# XMOS.net
KiCad netlist of a schematic drawn in Altium Designer
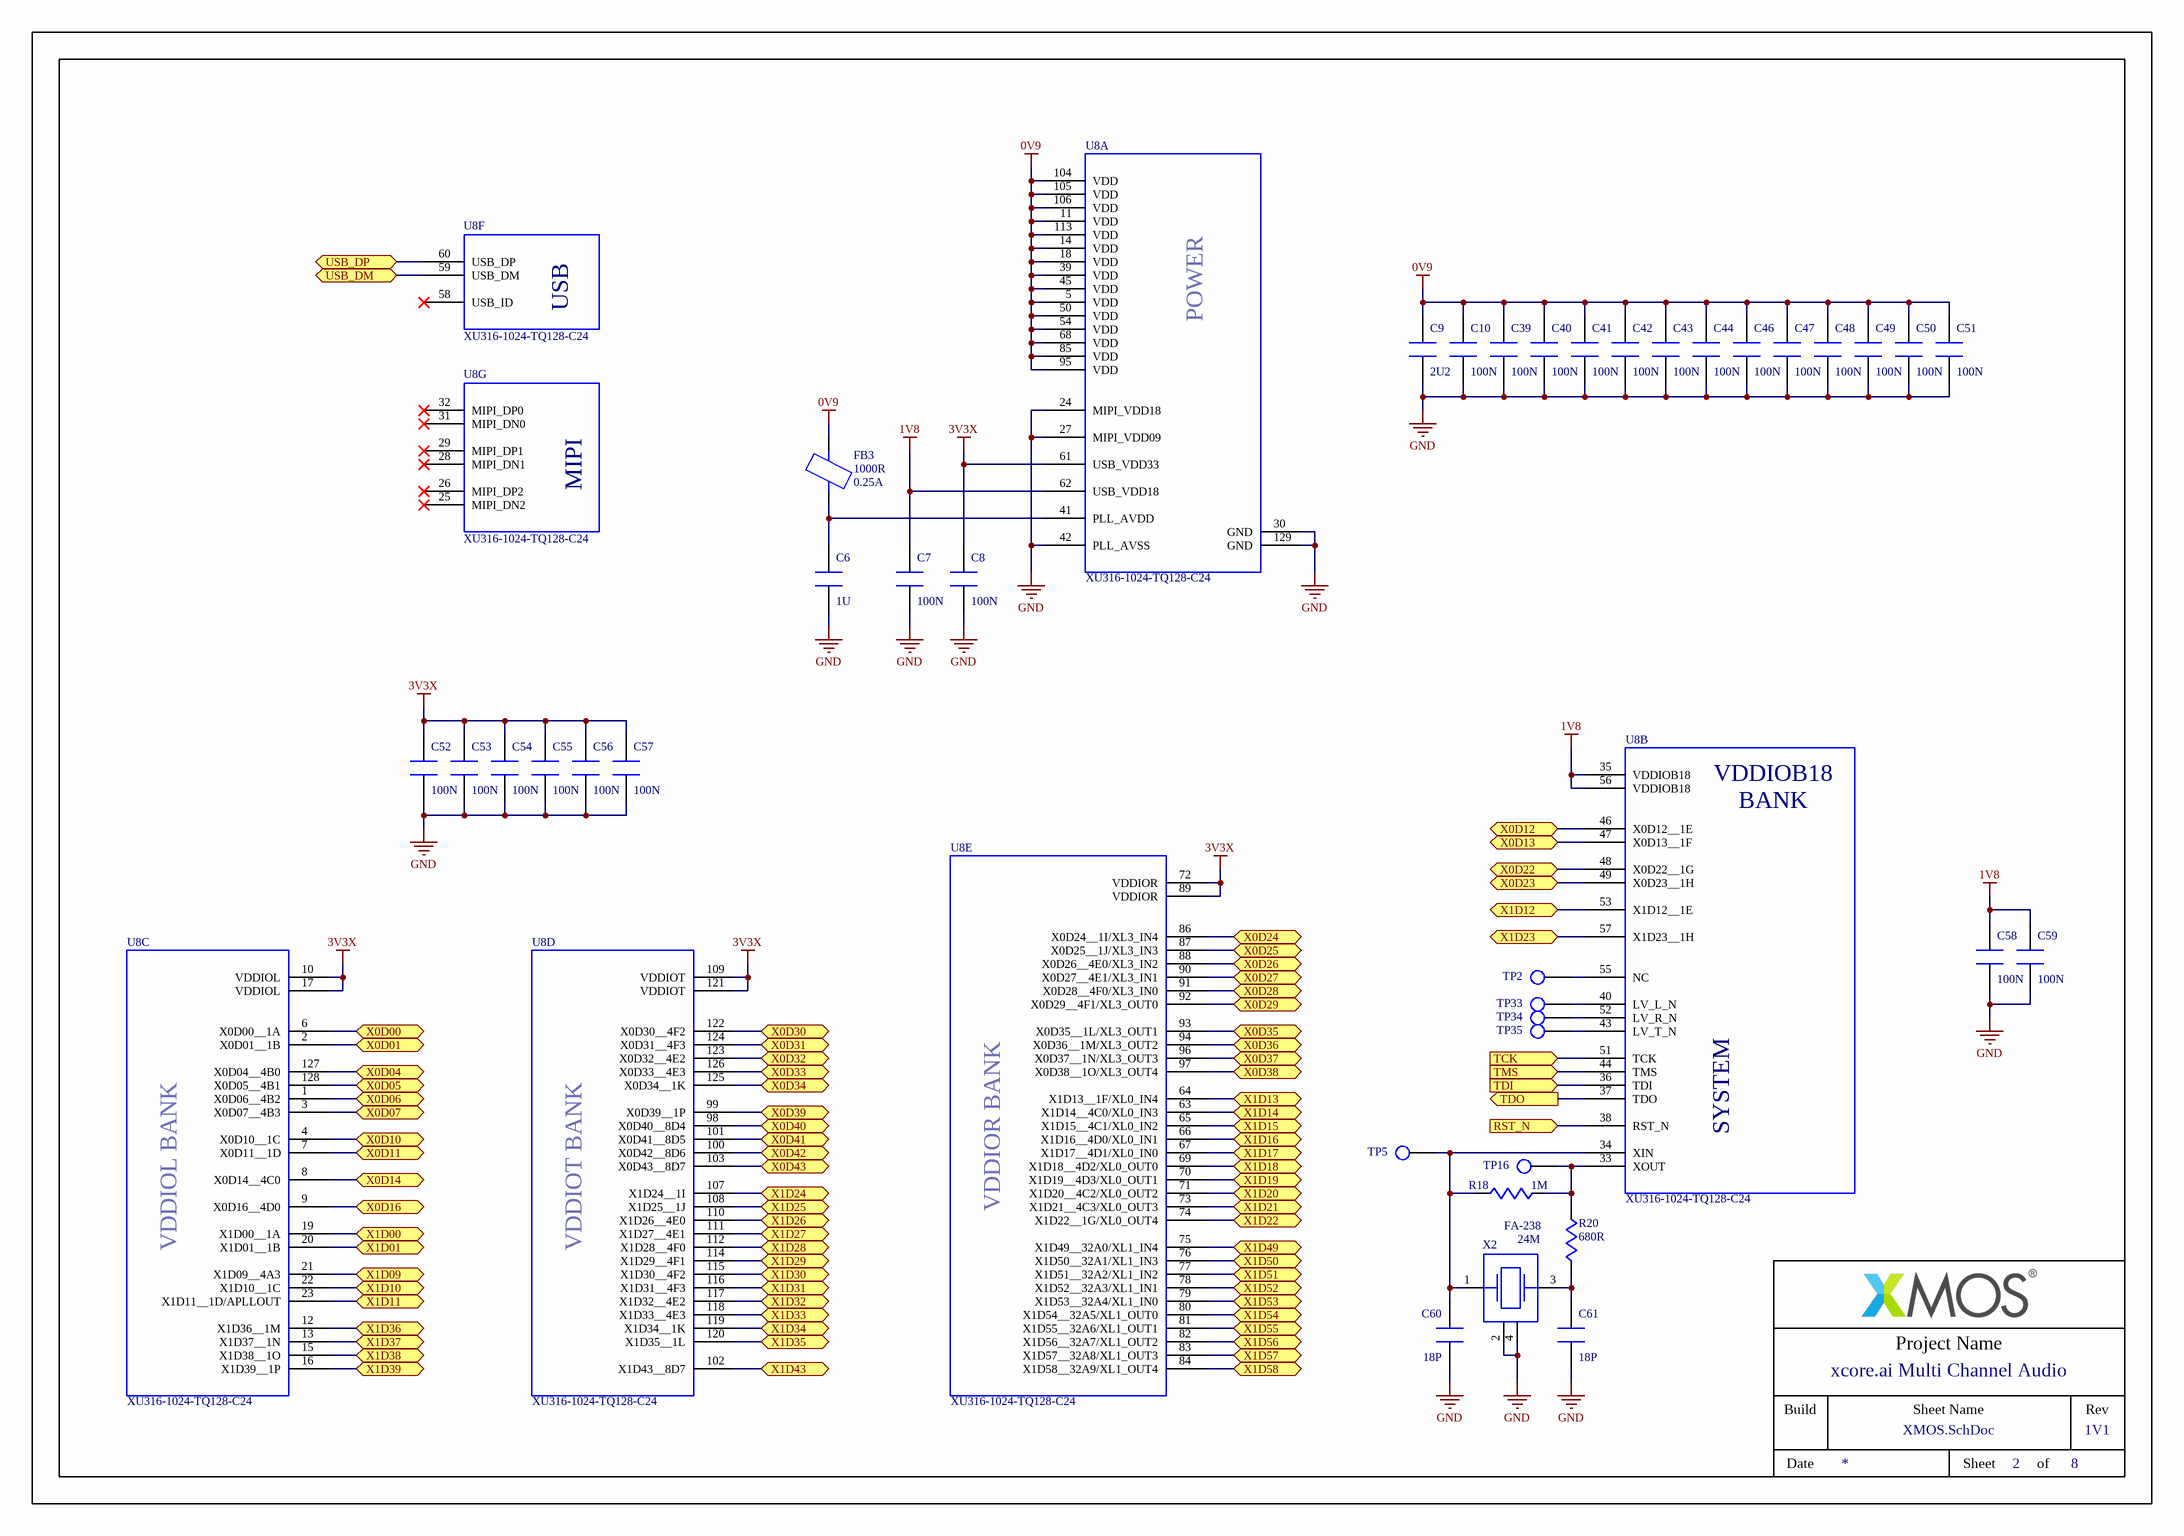
[diagram p0: XMOS.SchDoc]

(export (version "E")
  (design (tool "Eeschema 10.0.6"))
  (components
    (comp (ref "C6")
      (value "1U")
      (footprint "CAPC1005X55N")
      (description "CHIP CAPACITOR, CERAMIC, 1.0UF, 16V, 10%, X5R, 0402")
      (fields (field (name "PART NUMBER") "STD-06-0140") (field (name "TOLERANCE") "20%"))
      (libsource (lib "JG_StandardLibrary") (part "CAP_NP"))
    )
    (comp (ref "C7")
      (value "100N")
      (footprint "CAPC1005X55N")
      (description "CHIP CAPACITOR, CERAMIC, 100NF, 16V, 10%, X7R, 0402")
      (fields (field (name "PART NUMBER") "STD-06-0048") (field (name "TOLERANCE") "10%"))
      (libsource (lib "JG_StandardLibrary") (part "CAP_NP"))
    )
    (comp (ref "C8")
      (value "100N")
      (footprint "CAPC1005X55N")
      (description "CHIP CAPACITOR, CERAMIC, 100NF, 16V, 10%, X7R, 0402")
      (fields (field (name "PART NUMBER") "STD-06-0048") (field (name "TOLERANCE") "10%"))
      (libsource (lib "JG_StandardLibrary") (part "CAP_NP"))
    )
    (comp (ref "C9")
      (value "2U2")
      (footprint "CAPC1005X55N")
      (description "CHIP CAPACITOR, CERAMIC, 2.2UF, 6.3V, 10%, X5R, 0402")
      (fields (field (name "PART NUMBER") "GEN-03-0029") (field (name "TOLERANCE") "10%"))
      (libsource (lib "JG_GeneralLibrary") (part "CAP_NP"))
    )
    (comp (ref "C10")
      (value "100N")
      (footprint "CAPC1005X55N")
      (description "CHIP CAPACITOR, CERAMIC, 100NF, 16V, 10%, X7R, 0402")
      (fields (field (name "PART NUMBER") "STD-06-0048") (field (name "TOLERANCE") "10%"))
      (libsource (lib "JG_StandardLibrary") (part "CAP_NP"))
    )
    (comp (ref "C39")
      (value "100N")
      (footprint "CAPC1005X55N")
      (description "CHIP CAPACITOR, CERAMIC, 100NF, 16V, 10%, X7R, 0402")
      (fields (field (name "PART NUMBER") "STD-06-0048") (field (name "TOLERANCE") "10%"))
      (libsource (lib "JG_StandardLibrary") (part "CAP_NP"))
    )
    (comp (ref "C40")
      (value "100N")
      (footprint "CAPC1005X55N")
      (description "CHIP CAPACITOR, CERAMIC, 100NF, 16V, 10%, X7R, 0402")
      (fields (field (name "PART NUMBER") "STD-06-0048") (field (name "TOLERANCE") "10%"))
      (libsource (lib "JG_StandardLibrary") (part "CAP_NP"))
    )
    (comp (ref "C41")
      (value "100N")
      (footprint "CAPC1005X55N")
      (description "CHIP CAPACITOR, CERAMIC, 100NF, 16V, 10%, X7R, 0402")
      (fields (field (name "PART NUMBER") "STD-06-0048") (field (name "TOLERANCE") "10%"))
      (libsource (lib "JG_StandardLibrary") (part "CAP_NP"))
    )
    (comp (ref "C42")
      (value "100N")
      (footprint "CAPC1005X55N")
      (description "CHIP CAPACITOR, CERAMIC, 100NF, 16V, 10%, X7R, 0402")
      (fields (field (name "PART NUMBER") "STD-06-0048") (field (name "TOLERANCE") "10%"))
      (libsource (lib "JG_StandardLibrary") (part "CAP_NP"))
    )
    (comp (ref "C43")
      (value "100N")
      (footprint "CAPC1005X55N")
      (description "CHIP CAPACITOR, CERAMIC, 100NF, 16V, 10%, X7R, 0402")
      (fields (field (name "PART NUMBER") "STD-06-0048") (field (name "TOLERANCE") "10%"))
      (libsource (lib "JG_StandardLibrary") (part "CAP_NP"))
    )
    (comp (ref "C44")
      (value "100N")
      (footprint "CAPC1005X55N")
      (description "CHIP CAPACITOR, CERAMIC, 100NF, 16V, 10%, X7R, 0402")
      (fields (field (name "PART NUMBER") "STD-06-0048") (field (name "TOLERANCE") "10%"))
      (libsource (lib "JG_StandardLibrary") (part "CAP_NP"))
    )
    (comp (ref "C46")
      (value "100N")
      (footprint "CAPC1005X55N")
      (description "CHIP CAPACITOR, CERAMIC, 100NF, 16V, 10%, X7R, 0402")
      (fields (field (name "PART NUMBER") "STD-06-0048") (field (name "TOLERANCE") "10%"))
      (libsource (lib "JG_StandardLibrary") (part "CAP_NP"))
    )
    (comp (ref "C47")
      (value "100N")
      (footprint "CAPC1005X55N")
      (description "CHIP CAPACITOR, CERAMIC, 100NF, 16V, 10%, X7R, 0402")
      (fields (field (name "PART NUMBER") "STD-06-0048") (field (name "TOLERANCE") "10%"))
      (libsource (lib "JG_StandardLibrary") (part "CAP_NP"))
    )
    (comp (ref "C48")
      (value "100N")
      (footprint "CAPC1005X55N")
      (description "CHIP CAPACITOR, CERAMIC, 100NF, 16V, 10%, X7R, 0402")
      (fields (field (name "PART NUMBER") "STD-06-0048") (field (name "TOLERANCE") "10%"))
      (libsource (lib "JG_StandardLibrary") (part "CAP_NP"))
    )
    (comp (ref "C49")
      (value "100N")
      (footprint "CAPC1005X55N")
      (description "CHIP CAPACITOR, CERAMIC, 100NF, 16V, 10%, X7R, 0402")
      (fields (field (name "PART NUMBER") "STD-06-0048") (field (name "TOLERANCE") "10%"))
      (libsource (lib "JG_StandardLibrary") (part "CAP_NP"))
    )
    (comp (ref "C50")
      (value "100N")
      (footprint "CAPC1005X55N")
      (description "CHIP CAPACITOR, CERAMIC, 100NF, 16V, 10%, X7R, 0402")
      (fields (field (name "PART NUMBER") "STD-06-0048") (field (name "TOLERANCE") "10%"))
      (libsource (lib "JG_StandardLibrary") (part "CAP_NP"))
    )
    (comp (ref "C51")
      (value "100N")
      (footprint "CAPC1005X55N")
      (description "CHIP CAPACITOR, CERAMIC, 100NF, 16V, 10%, X7R, 0402")
      (fields (field (name "PART NUMBER") "STD-06-0048") (field (name "TOLERANCE") "10%"))
      (libsource (lib "JG_StandardLibrary") (part "CAP_NP"))
    )
    (comp (ref "C52")
      (value "100N")
      (footprint "CAPC1005X55N")
      (description "CHIP CAPACITOR, CERAMIC, 100NF, 16V, 10%, X7R, 0402")
      (fields (field (name "PART NUMBER") "STD-06-0048") (field (name "TOLERANCE") "10%"))
      (libsource (lib "JG_StandardLibrary") (part "CAP_NP"))
    )
    (comp (ref "C53")
      (value "100N")
      (footprint "CAPC1005X55N")
      (description "CHIP CAPACITOR, CERAMIC, 100NF, 16V, 10%, X7R, 0402")
      (fields (field (name "PART NUMBER") "STD-06-0048") (field (name "TOLERANCE") "10%"))
      (libsource (lib "JG_StandardLibrary") (part "CAP_NP"))
    )
    (comp (ref "C54")
      (value "100N")
      (footprint "CAPC1005X55N")
      (description "CHIP CAPACITOR, CERAMIC, 100NF, 16V, 10%, X7R, 0402")
      (fields (field (name "PART NUMBER") "STD-06-0048") (field (name "TOLERANCE") "10%"))
      (libsource (lib "JG_StandardLibrary") (part "CAP_NP"))
    )
    (comp (ref "C55")
      (value "100N")
      (footprint "CAPC1005X55N")
      (description "CHIP CAPACITOR, CERAMIC, 100NF, 16V, 10%, X7R, 0402")
      (fields (field (name "PART NUMBER") "STD-06-0048") (field (name "TOLERANCE") "10%"))
      (libsource (lib "JG_StandardLibrary") (part "CAP_NP"))
    )
    (comp (ref "C56")
      (value "100N")
      (footprint "CAPC1005X55N")
      (description "CHIP CAPACITOR, CERAMIC, 100NF, 16V, 10%, X7R, 0402")
      (fields (field (name "PART NUMBER") "STD-06-0048") (field (name "TOLERANCE") "10%"))
      (libsource (lib "JG_StandardLibrary") (part "CAP_NP"))
    )
    (comp (ref "C57")
      (value "100N")
      (footprint "CAPC1005X55N")
      (description "CHIP CAPACITOR, CERAMIC, 100NF, 16V, 10%, X7R, 0402")
      (fields (field (name "PART NUMBER") "STD-06-0048") (field (name "TOLERANCE") "10%"))
      (libsource (lib "JG_StandardLibrary") (part "CAP_NP"))
    )
    (comp (ref "C58")
      (value "100N")
      (footprint "CAPC1005X55N")
      (description "CHIP CAPACITOR, CERAMIC, 100NF, 16V, 10%, X7R, 0402")
      (fields (field (name "PART NUMBER") "STD-06-0048") (field (name "TOLERANCE") "10%"))
      (libsource (lib "JG_StandardLibrary") (part "CAP_NP"))
    )
    (comp (ref "C59")
      (value "100N")
      (footprint "CAPC1005X55N")
      (description "CHIP CAPACITOR, CERAMIC, 100NF, 16V, 10%, X7R, 0402")
      (fields (field (name "PART NUMBER") "STD-06-0048") (field (name "TOLERANCE") "10%"))
      (libsource (lib "JG_StandardLibrary") (part "CAP_NP"))
    )
    (comp (ref "C60")
      (value "18P")
      (footprint "CAPC1005X55N")
      (description "CHIP CAPACITOR, CERAMIC, 18PF, 50V, 5%, NP0, 0402")
      (fields (field (name "PART NUMBER") "STD-06-0016") (field (name "TOLERANCE") "5%"))
      (libsource (lib "JG_StandardLibrary") (part "CAP_NP"))
    )
    (comp (ref "C61")
      (value "18P")
      (footprint "CAPC1005X55N")
      (description "CHIP CAPACITOR, CERAMIC, 18PF, 50V, 5%, NP0, 0402")
      (fields (field (name "PART NUMBER") "STD-06-0016") (field (name "TOLERANCE") "5%"))
      (libsource (lib "JG_StandardLibrary") (part "CAP_NP"))
    )
    (comp (ref "FB3")
      (value "1000R")
      (footprint "INDC1005X55N")
      (description "Ferrite Bead, 1000R AT 100MHz, For Signal Lines, 0402, 0.25A")
      (fields
        (field (name "PART NUMBER") "GEN-04-0019")
        (field (name "RATED CURRENT") "0.25A")
        (field (name "MANUFACTURER") "Murata")
      )
      (libsource (lib "JG_GeneralLibrary") (part "FERRITE"))
    )
    (comp (ref "R18")
      (value "1M")
      (footprint "RESC1608X55N")
      (description "CHIP RESISTOR, 1.0M OHM, 0.1W, 5%, 0603")
      (fields (field (name "PART NUMBER") "STD-02-0134") (field (name "TOLERANCE") "5%"))
      (libsource (lib "JG_StandardLibrary") (part "RES"))
    )
    (comp (ref "R20")
      (value "680R")
      (footprint "RESC1608X55N")
      (description "CHIP RESISTOR, 680 OHM, 0.1W, 1%, 0603")
      (fields (field (name "PART NUMBER") "STD-02-0058") (field (name "TOLERANCE") "1%"))
      (libsource (lib "JG_StandardLibrary") (part "RES"))
    )
    (comp (ref "TP2")
      (value "TESTPOINT")
      (footprint "TESTPOINT_SMD_0.9MM_L")
      (description "Testpoint, SMD, 0.9mm")
      (fields (field (name "PART NUMBER") "GEN-24-0019") (field (name "MANUFACTURER") "NA"))
      (libsource (lib "JG_GeneralLibrary") (part "TESTPOINT"))
    )
    (comp (ref "TP5")
      (value "TESTPOINT")
      (footprint "TESTPOINT_SMD_0.9MM_L")
      (description "Testpoint, SMD, 0.9mm")
      (fields (field (name "PART NUMBER") "GEN-24-0019") (field (name "MANUFACTURER") "NA"))
      (libsource (lib "JG_GeneralLibrary") (part "TESTPOINT"))
    )
    (comp (ref "TP16")
      (value "TESTPOINT")
      (footprint "TESTPOINT_SMD_0.9MM_L")
      (description "Testpoint, SMD, 0.9mm")
      (fields (field (name "PART NUMBER") "GEN-24-0019") (field (name "MANUFACTURER") "NA"))
      (libsource (lib "JG_GeneralLibrary") (part "TESTPOINT"))
    )
    (comp (ref "TP33")
      (value "TESTPOINT")
      (footprint "TESTPOINT_SMD_0.9MM_L")
      (description "Testpoint, SMD, 0.9mm")
      (fields (field (name "PART NUMBER") "GEN-24-0019") (field (name "MANUFACTURER") "NA"))
      (libsource (lib "JG_GeneralLibrary") (part "TESTPOINT"))
    )
    (comp (ref "TP34")
      (value "TESTPOINT")
      (footprint "TESTPOINT_SMD_0.9MM_L")
      (description "Testpoint, SMD, 0.9mm")
      (fields (field (name "PART NUMBER") "GEN-24-0019") (field (name "MANUFACTURER") "NA"))
      (libsource (lib "JG_GeneralLibrary") (part "TESTPOINT"))
    )
    (comp (ref "TP35")
      (value "TESTPOINT")
      (footprint "TESTPOINT_SMD_0.9MM_L")
      (description "Testpoint, SMD, 0.9mm")
      (fields (field (name "PART NUMBER") "GEN-24-0019") (field (name "MANUFACTURER") "NA"))
      (libsource (lib "JG_GeneralLibrary") (part "TESTPOINT"))
    )
    (comp (ref "U8")
      (value "XU316-1024-TQ128-C24")
      (footprint "QFP40P1600X1600X120-129_T480N")
      (description "Processor, xcore.ai, 2400MIPS, 128TQFP")
      (fields (field (name "PART NUMBER") "GEN-08-0039") (field (name "MANUFACTURER") "XMOS"))
      (libsource (lib "JG_GeneralLibrary") (part "XMOS_XU316_1024_TQ128"))
    )
    (comp (ref "X2")
      (value "FA-238")
      (footprint "OSCCC320X250X120N")
      (description "Crystal, 24MHz, Freq Tol. ±30ppm, Freq Stab. ±30ppm, CL 12pF, 3.2x2.5mm SMD")
      (fields
        (field (name "FREQUENCY") "24M")
        (field (name "PART NUMBER") "GEN-15-0032")
        (field (name "MANUFACTURER") "Seiko Epson")
      )
      (libsource (lib "JG_GeneralLibrary") (part "CRYSTAL_4PIN_A"))
    )
  )
  (nets
    (net (code "1") (name "/RST_N") (class "Default")
      (node (ref "U8") (pin "38") (pinfunction "RST_N_38") (pintype "passive"))
    )
    (net (code "2") (name "/TCK") (class "Default")
      (node (ref "U8") (pin "51") (pinfunction "TCK_51") (pintype "passive"))
    )
    (net (code "3") (name "/TDI") (class "Default")
      (node (ref "U8") (pin "36") (pinfunction "TDI_36") (pintype "passive"))
    )
    (net (code "4") (name "/TDO") (class "Default")
      (node (ref "U8") (pin "37") (pinfunction "TDO_37") (pintype "passive"))
    )
    (net (code "5") (name "/TMS") (class "Default")
      (node (ref "U8") (pin "44") (pinfunction "TMS_44") (pintype "passive"))
    )
    (net (code "6") (name "/USB_DM") (class "Default")
      (node (ref "U8") (pin "59") (pinfunction "USB_DM_59") (pintype "passive"))
    )
    (net (code "7") (name "/USB_DP") (class "Default")
      (node (ref "U8") (pin "60") (pinfunction "USB_DP_60") (pintype "passive"))
    )
    (net (code "8") (name "/X0D00") (class "Default")
      (node (ref "U8") (pin "6") (pinfunction "X0D00__1A_6") (pintype "passive"))
    )
    (net (code "9") (name "/X0D01") (class "Default")
      (node (ref "U8") (pin "2") (pinfunction "X0D01__1B_2") (pintype "passive"))
    )
    (net (code "10") (name "/X0D04") (class "Default")
      (node (ref "U8") (pin "127") (pinfunction "X0D04__4B0_127") (pintype "passive"))
    )
    (net (code "11") (name "/X0D05") (class "Default")
      (node (ref "U8") (pin "128") (pinfunction "X0D05__4B1_128") (pintype "passive"))
    )
    (net (code "12") (name "/X0D06") (class "Default")
      (node (ref "U8") (pin "1") (pinfunction "X0D06__4B2_1") (pintype "passive"))
    )
    (net (code "13") (name "/X0D07") (class "Default")
      (node (ref "U8") (pin "3") (pinfunction "X0D07__4B3_3") (pintype "passive"))
    )
    (net (code "14") (name "/X0D10") (class "Default")
      (node (ref "U8") (pin "4") (pinfunction "X0D10__1C_4") (pintype "passive"))
    )
    (net (code "15") (name "/X0D11") (class "Default")
      (node (ref "U8") (pin "7") (pinfunction "X0D11__1D_7") (pintype "passive"))
    )
    (net (code "16") (name "/X0D12") (class "Default")
      (node (ref "U8") (pin "46") (pinfunction "X0D12__1E_46") (pintype "passive"))
    )
    (net (code "17") (name "/X0D13") (class "Default")
      (node (ref "U8") (pin "47") (pinfunction "X0D13__1F_47") (pintype "passive"))
    )
    (net (code "18") (name "/X0D14") (class "Default")
      (node (ref "U8") (pin "8") (pinfunction "X0D14__4C0_8") (pintype "passive"))
    )
    (net (code "19") (name "/X0D16") (class "Default")
      (node (ref "U8") (pin "9") (pinfunction "X0D16__4D0_9") (pintype "passive"))
    )
    (net (code "20") (name "/X0D22") (class "Default")
      (node (ref "U8") (pin "48") (pinfunction "X0D22__1G_48") (pintype "passive"))
    )
    (net (code "21") (name "/X0D23") (class "Default")
      (node (ref "U8") (pin "49") (pinfunction "X0D23__1H_49") (pintype "passive"))
    )
    (net (code "22") (name "/X0D24") (class "Default")
      (node (ref "U8") (pin "86") (pinfunction "X0D24__1I/XL3_IN4_86") (pintype "passive"))
    )
    (net (code "23") (name "/X0D25") (class "Default")
      (node (ref "U8") (pin "87") (pinfunction "X0D25__1J/XL3_IN3_87") (pintype "passive"))
    )
    (net (code "24") (name "/X0D26") (class "Default")
      (node (ref "U8") (pin "88") (pinfunction "X0D26__4E0/XL3_IN2_88") (pintype "passive"))
    )
    (net (code "25") (name "/X0D27") (class "Default")
      (node (ref "U8") (pin "90") (pinfunction "X0D27__4E1/XL3_IN1_90") (pintype "passive"))
    )
    (net (code "26") (name "/X0D28") (class "Default")
      (node (ref "U8") (pin "91") (pinfunction "X0D28__4F0/XL3_IN0_91") (pintype "passive"))
    )
    (net (code "27") (name "/X0D29") (class "Default")
      (node (ref "U8") (pin "92") (pinfunction "X0D29__4F1/XL3_OUT0_92") (pintype "passive"))
    )
    (net (code "28") (name "/X0D30") (class "Default")
      (node (ref "U8") (pin "122") (pinfunction "X0D30__4F2_122") (pintype "passive"))
    )
    (net (code "29") (name "/X0D31") (class "Default")
      (node (ref "U8") (pin "124") (pinfunction "X0D31__4F3_124") (pintype "passive"))
    )
    (net (code "30") (name "/X0D32") (class "Default")
      (node (ref "U8") (pin "123") (pinfunction "X0D32__4E2_123") (pintype "passive"))
    )
    (net (code "31") (name "/X0D33") (class "Default")
      (node (ref "U8") (pin "126") (pinfunction "X0D33__4E3_126") (pintype "passive"))
    )
    (net (code "32") (name "/X0D34") (class "Default")
      (node (ref "U8") (pin "125") (pinfunction "X0D34__1K_125") (pintype "passive"))
    )
    (net (code "33") (name "/X0D35") (class "Default")
      (node (ref "U8") (pin "93") (pinfunction "X0D35__1L/XL3_OUT1_93") (pintype "passive"))
    )
    (net (code "34") (name "/X0D36") (class "Default")
      (node (ref "U8") (pin "94") (pinfunction "X0D36__1M/XL3_OUT2_94") (pintype "passive"))
    )
    (net (code "35") (name "/X0D37") (class "Default")
      (node (ref "U8") (pin "96") (pinfunction "X0D37__1N/XL3_OUT3_96") (pintype "passive"))
    )
    (net (code "36") (name "/X0D38") (class "Default")
      (node (ref "U8") (pin "97") (pinfunction "X0D38__1O/XL3_OUT4_97") (pintype "passive"))
    )
    (net (code "37") (name "/X0D39") (class "Default")
      (node (ref "U8") (pin "99") (pinfunction "X0D39__1P_99") (pintype "passive"))
    )
    (net (code "38") (name "/X0D40") (class "Default")
      (node (ref "U8") (pin "98") (pinfunction "X0D40__8D4_98") (pintype "passive"))
    )
    (net (code "39") (name "/X0D41") (class "Default")
      (node (ref "U8") (pin "101") (pinfunction "X0D41__8D5_101") (pintype "passive"))
    )
    (net (code "40") (name "/X0D42") (class "Default")
      (node (ref "U8") (pin "100") (pinfunction "X0D42__8D6_100") (pintype "passive"))
    )
    (net (code "41") (name "/X0D43") (class "Default")
      (node (ref "U8") (pin "103") (pinfunction "X0D43__8D7_103") (pintype "passive"))
    )
    (net (code "42") (name "/X1D00") (class "Default")
      (node (ref "U8") (pin "19") (pinfunction "X1D00__1A_19") (pintype "passive"))
    )
    (net (code "43") (name "/X1D01") (class "Default")
      (node (ref "U8") (pin "20") (pinfunction "X1D01__1B_20") (pintype "passive"))
    )
    (net (code "44") (name "/X1D09") (class "Default")
      (node (ref "U8") (pin "21") (pinfunction "X1D09__4A3_21") (pintype "passive"))
    )
    (net (code "45") (name "/X1D10") (class "Default")
      (node (ref "U8") (pin "22") (pinfunction "X1D10__1C_22") (pintype "passive"))
    )
    (net (code "46") (name "/X1D11") (class "Default")
      (node (ref "U8") (pin "23") (pinfunction "X1D11__1D/APLLOUT_23") (pintype "passive"))
    )
    (net (code "47") (name "/X1D12") (class "Default")
      (node (ref "U8") (pin "53") (pinfunction "X1D12__1E_53") (pintype "passive"))
    )
    (net (code "48") (name "/X1D13") (class "Default")
      (node (ref "U8") (pin "64") (pinfunction "X1D13__1F/XL0_IN4_64") (pintype "passive"))
    )
    (net (code "49") (name "/X1D14") (class "Default")
      (node (ref "U8") (pin "63") (pinfunction "X1D14__4C0/XL0_IN3_63") (pintype "passive"))
    )
    (net (code "50") (name "/X1D15") (class "Default")
      (node (ref "U8") (pin "65") (pinfunction "X1D15__4C1/XL0_IN2_65") (pintype "passive"))
    )
    (net (code "51") (name "/X1D16") (class "Default")
      (node (ref "U8") (pin "66") (pinfunction "X1D16__4D0/XL0_IN1_66") (pintype "passive"))
    )
    (net (code "52") (name "/X1D17") (class "Default")
      (node (ref "U8") (pin "67") (pinfunction "X1D17__4D1/XL0_IN0_67") (pintype "passive"))
    )
    (net (code "53") (name "/X1D18") (class "Default")
      (node (ref "U8") (pin "69") (pinfunction "X1D18__4D2/XL0_OUT0_69") (pintype "passive"))
    )
    (net (code "54") (name "/X1D19") (class "Default")
      (node (ref "U8") (pin "70") (pinfunction "X1D19__4D3/XL0_OUT1_70") (pintype "passive"))
    )
    (net (code "55") (name "/X1D20") (class "Default")
      (node (ref "U8") (pin "71") (pinfunction "X1D20__4C2/XL0_OUT2_71") (pintype "passive"))
    )
    (net (code "56") (name "/X1D21") (class "Default")
      (node (ref "U8") (pin "73") (pinfunction "X1D21__4C3/XL0_OUT3_73") (pintype "passive"))
    )
    (net (code "57") (name "/X1D22") (class "Default")
      (node (ref "U8") (pin "74") (pinfunction "X1D22__1G/XL0_OUT4_74") (pintype "passive"))
    )
    (net (code "58") (name "/X1D23") (class "Default")
      (node (ref "U8") (pin "57") (pinfunction "X1D23__1H_57") (pintype "passive"))
    )
    (net (code "59") (name "/X1D24") (class "Default")
      (node (ref "U8") (pin "107") (pinfunction "X1D24__1I_107") (pintype "passive"))
    )
    (net (code "60") (name "/X1D25") (class "Default")
      (node (ref "U8") (pin "108") (pinfunction "X1D25__1J_108") (pintype "passive"))
    )
    (net (code "61") (name "/X1D26") (class "Default")
      (node (ref "U8") (pin "110") (pinfunction "X1D26__4E0_110") (pintype "passive"))
    )
    (net (code "62") (name "/X1D27") (class "Default")
      (node (ref "U8") (pin "111") (pinfunction "X1D27__4E1_111") (pintype "passive"))
    )
    (net (code "63") (name "/X1D28") (class "Default")
      (node (ref "U8") (pin "112") (pinfunction "X1D28__4F0_112") (pintype "passive"))
    )
    (net (code "64") (name "/X1D29") (class "Default")
      (node (ref "U8") (pin "114") (pinfunction "X1D29__4F1_114") (pintype "passive"))
    )
    (net (code "65") (name "/X1D30") (class "Default")
      (node (ref "U8") (pin "115") (pinfunction "X1D30__4F2_115") (pintype "passive"))
    )
    (net (code "66") (name "/X1D31") (class "Default")
      (node (ref "U8") (pin "116") (pinfunction "X1D31__4F3_116") (pintype "passive"))
    )
    (net (code "67") (name "/X1D32") (class "Default")
      (node (ref "U8") (pin "117") (pinfunction "X1D32__4E2_117") (pintype "passive"))
    )
    (net (code "68") (name "/X1D33") (class "Default")
      (node (ref "U8") (pin "118") (pinfunction "X1D33__4E3_118") (pintype "passive"))
    )
    (net (code "69") (name "/X1D34") (class "Default")
      (node (ref "U8") (pin "119") (pinfunction "X1D34__1K_119") (pintype "passive"))
    )
    (net (code "70") (name "/X1D35") (class "Default")
      (node (ref "U8") (pin "120") (pinfunction "X1D35__1L_120") (pintype "passive"))
    )
    (net (code "71") (name "/X1D36") (class "Default")
      (node (ref "U8") (pin "12") (pinfunction "X1D36__1M_12") (pintype "passive"))
    )
    (net (code "72") (name "/X1D37") (class "Default")
      (node (ref "U8") (pin "13") (pinfunction "X1D37__1N_13") (pintype "passive"))
    )
    (net (code "73") (name "/X1D38") (class "Default")
      (node (ref "U8") (pin "15") (pinfunction "X1D38__1O_15") (pintype "passive"))
    )
    (net (code "74") (name "/X1D39") (class "Default")
      (node (ref "U8") (pin "16") (pinfunction "X1D39__1P_16") (pintype "passive"))
    )
    (net (code "75") (name "/X1D43") (class "Default")
      (node (ref "U8") (pin "102") (pinfunction "X1D43__8D7_102") (pintype "passive"))
    )
    (net (code "76") (name "/X1D49") (class "Default")
      (node (ref "U8") (pin "75") (pinfunction "X1D49__32A0/XL1_IN4_75") (pintype "passive"))
    )
    (net (code "77") (name "/X1D50") (class "Default")
      (node (ref "U8") (pin "76") (pinfunction "X1D50__32A1/XL1_IN3_76") (pintype "passive"))
    )
    (net (code "78") (name "/X1D51") (class "Default")
      (node (ref "U8") (pin "77") (pinfunction "X1D51__32A2/XL1_IN2_77") (pintype "passive"))
    )
    (net (code "79") (name "/X1D52") (class "Default")
      (node (ref "U8") (pin "78") (pinfunction "X1D52__32A3/XL1_IN1_78") (pintype "passive"))
    )
    (net (code "80") (name "/X1D53") (class "Default")
      (node (ref "U8") (pin "79") (pinfunction "X1D53__32A4/XL1_IN0_79") (pintype "passive"))
    )
    (net (code "81") (name "/X1D54") (class "Default")
      (node (ref "U8") (pin "80") (pinfunction "X1D54__32A5/XL1_OUT0_80") (pintype "passive"))
    )
    (net (code "82") (name "/X1D55") (class "Default")
      (node (ref "U8") (pin "81") (pinfunction "X1D55__32A6/XL1_OUT1_81") (pintype "passive"))
    )
    (net (code "83") (name "/X1D56") (class "Default")
      (node (ref "U8") (pin "82") (pinfunction "X1D56__32A7/XL1_OUT2_82") (pintype "passive"))
    )
    (net (code "84") (name "/X1D57") (class "Default")
      (node (ref "U8") (pin "83") (pinfunction "X1D57__32A8/XL1_OUT3_83") (pintype "passive"))
    )
    (net (code "85") (name "/X1D58") (class "Default")
      (node (ref "U8") (pin "84") (pinfunction "X1D58__32A9/XL1_OUT4_84") (pintype "passive"))
    )
    (net (code "86") (name "0V9") (class "Default")
      (node (ref "C10") (pin "1") (pinfunction "1_1") (pintype "passive"))
      (node (ref "C39") (pin "1") (pinfunction "1_1") (pintype "passive"))
      (node (ref "C40") (pin "1") (pinfunction "1_1") (pintype "passive"))
      (node (ref "C41") (pin "1") (pinfunction "1_1") (pintype "passive"))
      (node (ref "C42") (pin "1") (pinfunction "1_1") (pintype "passive"))
      (node (ref "C43") (pin "1") (pinfunction "1_1") (pintype "passive"))
      (node (ref "C44") (pin "1") (pinfunction "1_1") (pintype "passive"))
      (node (ref "C46") (pin "1") (pinfunction "1_1") (pintype "passive"))
      (node (ref "C47") (pin "1") (pinfunction "1_1") (pintype "passive"))
      (node (ref "C48") (pin "1") (pinfunction "1_1") (pintype "passive"))
      (node (ref "C49") (pin "1") (pinfunction "1_1") (pintype "passive"))
      (node (ref "C50") (pin "1") (pinfunction "1_1") (pintype "passive"))
      (node (ref "C51") (pin "1") (pinfunction "1_1") (pintype "passive"))
      (node (ref "C9") (pin "1") (pinfunction "1_1") (pintype "passive"))
      (node (ref "FB3") (pin "2") (pinfunction "2_2") (pintype "passive"))
      (node (ref "U8") (pin "104") (pinfunction "VDD_104") (pintype "passive"))
      (node (ref "U8") (pin "105") (pinfunction "VDD_105") (pintype "passive"))
      (node (ref "U8") (pin "106") (pinfunction "VDD_106") (pintype "passive"))
      (node (ref "U8") (pin "11") (pinfunction "VDD_11") (pintype "passive"))
      (node (ref "U8") (pin "113") (pinfunction "VDD_113") (pintype "passive"))
      (node (ref "U8") (pin "14") (pinfunction "VDD_14") (pintype "passive"))
      (node (ref "U8") (pin "18") (pinfunction "VDD_18") (pintype "passive"))
      (node (ref "U8") (pin "39") (pinfunction "VDD_39") (pintype "passive"))
      (node (ref "U8") (pin "45") (pinfunction "VDD_45") (pintype "passive"))
      (node (ref "U8") (pin "5") (pinfunction "VDD_5") (pintype "passive"))
      (node (ref "U8") (pin "50") (pinfunction "VDD_50") (pintype "passive"))
      (node (ref "U8") (pin "54") (pinfunction "VDD_54") (pintype "passive"))
      (node (ref "U8") (pin "68") (pinfunction "VDD_68") (pintype "passive"))
      (node (ref "U8") (pin "85") (pinfunction "VDD_85") (pintype "passive"))
      (node (ref "U8") (pin "95") (pinfunction "VDD_95") (pintype "passive"))
    )
    (net (code "87") (name "1V8") (class "Default")
      (node (ref "C58") (pin "1") (pinfunction "1_1") (pintype "passive"))
      (node (ref "C59") (pin "1") (pinfunction "1_1") (pintype "passive"))
      (node (ref "C7") (pin "1") (pinfunction "1_1") (pintype "passive"))
      (node (ref "U8") (pin "35") (pinfunction "VDDIOB18_35") (pintype "passive"))
      (node (ref "U8") (pin "56") (pinfunction "VDDIOB18_56") (pintype "passive"))
      (node (ref "U8") (pin "62") (pinfunction "USB_VDD18_62") (pintype "passive"))
    )
    (net (code "88") (name "3V3X") (class "Default")
      (node (ref "C52") (pin "1") (pinfunction "1_1") (pintype "passive"))
      (node (ref "C53") (pin "1") (pinfunction "1_1") (pintype "passive"))
      (node (ref "C54") (pin "1") (pinfunction "1_1") (pintype "passive"))
      (node (ref "C55") (pin "1") (pinfunction "1_1") (pintype "passive"))
      (node (ref "C56") (pin "1") (pinfunction "1_1") (pintype "passive"))
      (node (ref "C57") (pin "1") (pinfunction "1_1") (pintype "passive"))
      (node (ref "C8") (pin "1") (pinfunction "1_1") (pintype "passive"))
      (node (ref "U8") (pin "10") (pinfunction "VDDIOL_10") (pintype "passive"))
      (node (ref "U8") (pin "109") (pinfunction "VDDIOT_109") (pintype "passive"))
      (node (ref "U8") (pin "121") (pinfunction "VDDIOT_121") (pintype "passive"))
      (node (ref "U8") (pin "17") (pinfunction "VDDIOL_17") (pintype "passive"))
      (node (ref "U8") (pin "61") (pinfunction "USB_VDD33_61") (pintype "passive"))
      (node (ref "U8") (pin "72") (pinfunction "VDDIOR_72") (pintype "passive"))
      (node (ref "U8") (pin "89") (pinfunction "VDDIOR_89") (pintype "passive"))
    )
    (net (code "89") (name "GND") (class "Default")
      (node (ref "C10") (pin "2") (pinfunction "2_2") (pintype "passive"))
      (node (ref "C39") (pin "2") (pinfunction "2_2") (pintype "passive"))
      (node (ref "C40") (pin "2") (pinfunction "2_2") (pintype "passive"))
      (node (ref "C41") (pin "2") (pinfunction "2_2") (pintype "passive"))
      (node (ref "C42") (pin "2") (pinfunction "2_2") (pintype "passive"))
      (node (ref "C43") (pin "2") (pinfunction "2_2") (pintype "passive"))
      (node (ref "C44") (pin "2") (pinfunction "2_2") (pintype "passive"))
      (node (ref "C46") (pin "2") (pinfunction "2_2") (pintype "passive"))
      (node (ref "C47") (pin "2") (pinfunction "2_2") (pintype "passive"))
      (node (ref "C48") (pin "2") (pinfunction "2_2") (pintype "passive"))
      (node (ref "C49") (pin "2") (pinfunction "2_2") (pintype "passive"))
      (node (ref "C50") (pin "2") (pinfunction "2_2") (pintype "passive"))
      (node (ref "C51") (pin "2") (pinfunction "2_2") (pintype "passive"))
      (node (ref "C52") (pin "2") (pinfunction "2_2") (pintype "passive"))
      (node (ref "C53") (pin "2") (pinfunction "2_2") (pintype "passive"))
      (node (ref "C54") (pin "2") (pinfunction "2_2") (pintype "passive"))
      (node (ref "C55") (pin "2") (pinfunction "2_2") (pintype "passive"))
      (node (ref "C56") (pin "2") (pinfunction "2_2") (pintype "passive"))
      (node (ref "C57") (pin "2") (pinfunction "2_2") (pintype "passive"))
      (node (ref "C58") (pin "2") (pinfunction "2_2") (pintype "passive"))
      (node (ref "C59") (pin "2") (pinfunction "2_2") (pintype "passive"))
      (node (ref "C6") (pin "2") (pinfunction "2_2") (pintype "passive"))
      (node (ref "C60") (pin "2") (pinfunction "2_2") (pintype "passive"))
      (node (ref "C61") (pin "2") (pinfunction "2_2") (pintype "passive"))
      (node (ref "C7") (pin "2") (pinfunction "2_2") (pintype "passive"))
      (node (ref "C8") (pin "2") (pinfunction "2_2") (pintype "passive"))
      (node (ref "C9") (pin "2") (pinfunction "2_2") (pintype "passive"))
      (node (ref "U8") (pin "129") (pinfunction "GND_129") (pintype "passive"))
      (node (ref "U8") (pin "24") (pinfunction "MIPI_VDD18_24") (pintype "passive"))
      (node (ref "U8") (pin "27") (pinfunction "MIPI_VDD09_27") (pintype "passive"))
      (node (ref "U8") (pin "30") (pinfunction "GND_30") (pintype "passive"))
      (node (ref "U8") (pin "42") (pinfunction "PLL_AVSS_42") (pintype "passive"))
      (node (ref "X2") (pin "2") (pinfunction "CASE_2_2") (pintype "passive"))
      (node (ref "X2") (pin "4") (pinfunction "CASE_4_4") (pintype "passive"))
    )
    (net (code "90") (name "Net-(U8A-PLL_AVDD)") (class "Default")
      (node (ref "C6") (pin "1") (pinfunction "1_1") (pintype "passive"))
      (node (ref "FB3") (pin "1") (pinfunction "1_1") (pintype "passive"))
      (node (ref "U8") (pin "41") (pinfunction "PLL_AVDD_41") (pintype "passive"))
    )
    (net (code "91") (name "Net-(U8B-LV_L_N)") (class "Default")
      (node (ref "TP33") (pin "1") (pinfunction "1_1") (pintype "passive"))
      (node (ref "U8") (pin "40") (pinfunction "LV_L_N_40") (pintype "passive"))
    )
    (net (code "92") (name "Net-(U8B-LV_R_N)") (class "Default")
      (node (ref "TP34") (pin "1") (pinfunction "1_1") (pintype "passive"))
      (node (ref "U8") (pin "52") (pinfunction "LV_R_N_52") (pintype "passive"))
    )
    (net (code "93") (name "Net-(U8B-LV_T_N)") (class "Default")
      (node (ref "TP35") (pin "1") (pinfunction "1_1") (pintype "passive"))
      (node (ref "U8") (pin "43") (pinfunction "LV_T_N_43") (pintype "passive"))
    )
    (net (code "94") (name "Net-(U8B-NC)") (class "Default")
      (node (ref "TP2") (pin "1") (pinfunction "1_1") (pintype "passive"))
      (node (ref "U8") (pin "55") (pinfunction "NC_55") (pintype "passive"))
    )
    (net (code "95") (name "Net-(U8B-XIN)") (class "Default")
      (node (ref "C60") (pin "1") (pinfunction "1_1") (pintype "passive"))
      (node (ref "R18") (pin "1") (pinfunction "1_1") (pintype "passive"))
      (node (ref "TP5") (pin "1") (pinfunction "1_1") (pintype "passive"))
      (node (ref "U8") (pin "34") (pinfunction "XIN_34") (pintype "passive"))
      (node (ref "X2") (pin "1") (pinfunction "A_1") (pintype "passive"))
    )
    (net (code "96") (name "Net-(U8B-XOUT)") (class "Default")
      (node (ref "R18") (pin "2") (pinfunction "2_2") (pintype "passive"))
      (node (ref "R20") (pin "2") (pinfunction "2_2") (pintype "passive"))
      (node (ref "TP16") (pin "1") (pinfunction "1_1") (pintype "passive"))
      (node (ref "U8") (pin "33") (pinfunction "XOUT_33") (pintype "passive"))
    )
    (net (code "97") (name "Net-(X2-B)") (class "Default")
      (node (ref "C61") (pin "1") (pinfunction "1_1") (pintype "passive"))
      (node (ref "R20") (pin "1") (pinfunction "1_1") (pintype "passive"))
      (node (ref "X2") (pin "3") (pinfunction "B_3") (pintype "passive"))
    )
    (net (code "98") (name "unconnected-(U8F-USB_ID-Pad58)") (class "Default")
      (node (ref "U8") (pin "58") (pinfunction "USB_ID_58") (pintype "passive+no_connect"))
    )
    (net (code "99") (name "unconnected-(U8G-MIPI_DN0-Pad31)") (class "Default")
      (node (ref "U8") (pin "31") (pinfunction "MIPI_DN0_31") (pintype "passive+no_connect"))
    )
    (net (code "100") (name "unconnected-(U8G-MIPI_DN1-Pad28)") (class "Default")
      (node (ref "U8") (pin "28") (pinfunction "MIPI_DN1_28") (pintype "passive+no_connect"))
    )
    (net (code "101") (name "unconnected-(U8G-MIPI_DN2-Pad25)") (class "Default")
      (node (ref "U8") (pin "25") (pinfunction "MIPI_DN2_25") (pintype "passive+no_connect"))
    )
    (net (code "102") (name "unconnected-(U8G-MIPI_DP0-Pad32)") (class "Default")
      (node (ref "U8") (pin "32") (pinfunction "MIPI_DP0_32") (pintype "passive+no_connect"))
    )
    (net (code "103") (name "unconnected-(U8G-MIPI_DP1-Pad29)") (class "Default")
      (node (ref "U8") (pin "29") (pinfunction "MIPI_DP1_29") (pintype "passive+no_connect"))
    )
    (net (code "104") (name "unconnected-(U8G-MIPI_DP2-Pad26)") (class "Default")
      (node (ref "U8") (pin "26") (pinfunction "MIPI_DP2_26") (pintype "passive+no_connect"))
    )
  )
)
